# Adafruit_Power_Switch.net
KiCad netlist of a schematic drawn in EAGLE
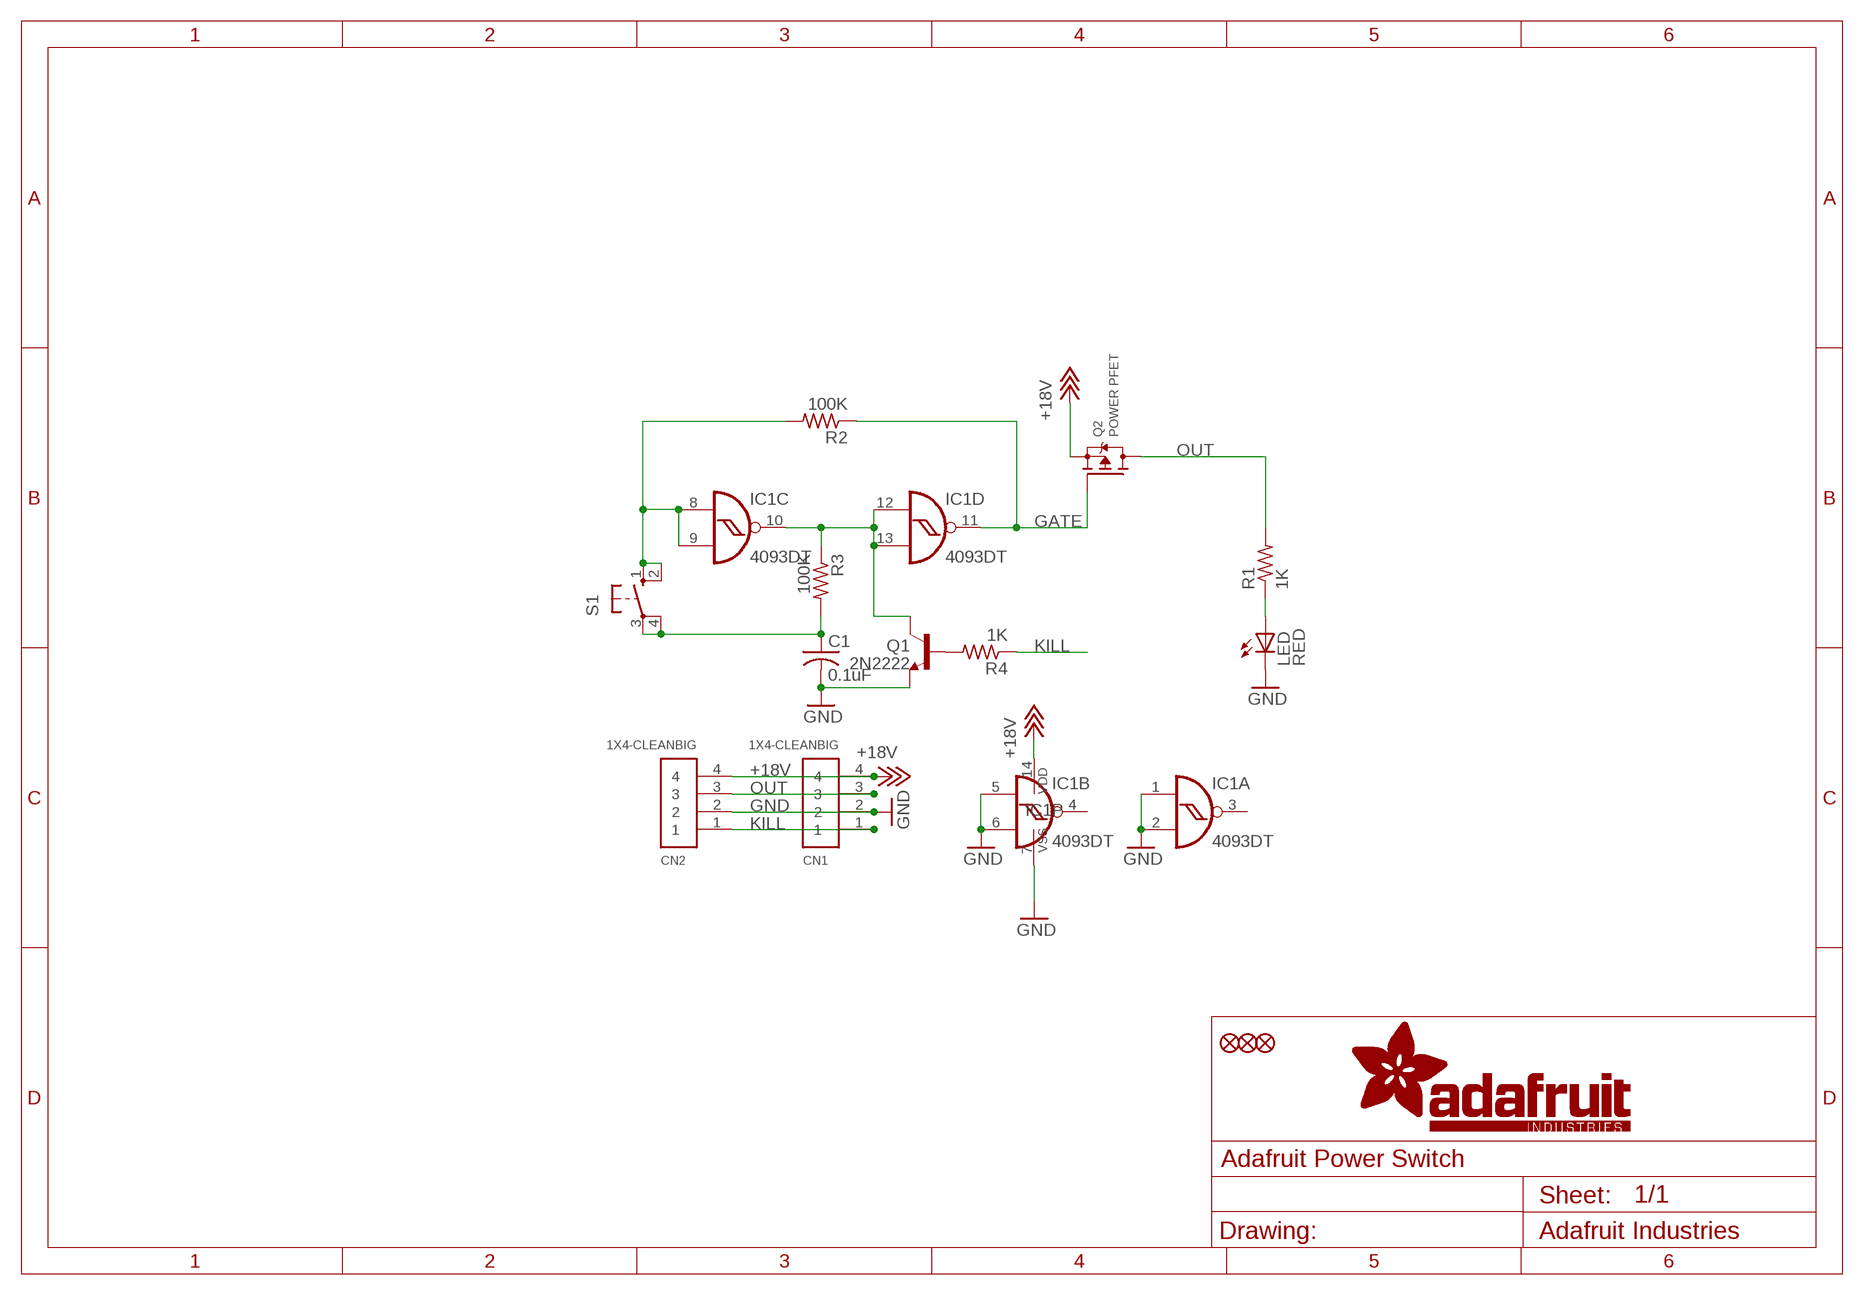
[diagram p0: schematic, sheet 1]

(export (version "E")
  (design (tool "Eeschema 10.0.6"))
  (components
    (comp (ref "C1")
      (value "0.1uF")
      (footprint "eagle-import:C0805")
      (libsource (lib "eagle-import") (part "C-USC0805"))
    )
    (comp (ref "CN1")
      (value "1X4-CLEANBIG")
      (footprint "eagle-import:1X04-CLEANBIG")
      (libsource (lib "eagle-import") (part "1X4-CLEANBIG"))
    )
    (comp (ref "CN2")
      (value "1X4-CLEANBIG")
      (footprint "eagle-import:1X04-CLEANBIG")
      (libsource (lib "eagle-import") (part "1X4-CLEANBIG"))
    )
    (comp (ref "FID1")
      (value "FIDUCIAL\"\"")
      (footprint "eagle-import:FIDUCIAL_1MM")
      (libsource (lib "eagle-import") (part "FIDUCIAL{dblquote}{dblquote}"))
    )
    (comp (ref "FID2")
      (value "FIDUCIAL\"\"")
      (footprint "eagle-import:FIDUCIAL_1MM")
      (libsource (lib "eagle-import") (part "FIDUCIAL{dblquote}{dblquote}"))
    )
    (comp (ref "FID3")
      (value "FIDUCIAL\"\"")
      (footprint "eagle-import:FIDUCIAL_1MM")
      (libsource (lib "eagle-import") (part "FIDUCIAL{dblquote}{dblquote}"))
    )
    (comp (ref "IC1")
      (value "4093DT")
      (footprint "eagle-import:MC14093B-TSSOP14")
      (libsource (lib "eagle-import") (part "4093DT"))
    )
    (comp (ref "LED")
      (value "RED")
      (footprint "eagle-import:CHIP-LED0805")
      (libsource (lib "eagle-import") (part "LEDCHIP-LED0805"))
    )
    (comp (ref "Q1")
      (value "2N2222")
      (footprint "eagle-import:SOT23-BEC")
      (libsource (lib "eagle-import") (part "-NPN-SOT23-BECMMBT2222ALT1"))
    )
    (comp (ref "Q2")
      (value "POWER PFET")
      (footprint "eagle-import:SOT23-WIDE")
      (libsource (lib "eagle-import") (part "MOSFET-PWIDE"))
    )
    (comp (ref "R1")
      (value "1K")
      (footprint "eagle-import:R0805")
      (libsource (lib "eagle-import") (part "rcl_R-US_R0805"))
    )
    (comp (ref "R2")
      (value "100K")
      (footprint "eagle-import:R0805")
      (libsource (lib "eagle-import") (part "rcl_R-US_R0805"))
    )
    (comp (ref "R3")
      (value "100K")
      (footprint "eagle-import:R0805")
      (libsource (lib "eagle-import") (part "rcl_R-US_R0805"))
    )
    (comp (ref "R4")
      (value "1K")
      (footprint "eagle-import:R0805")
      (libsource (lib "eagle-import") (part "R-US_R0805"))
    )
    (comp (ref "S1")
      (value "40-XX-ROUND")
      (footprint "eagle-import:B3F-40XX-ROUND")
      (libsource (lib "eagle-import") (part "40-XX-ROUND"))
    )
  )
  (nets
    (net (code "1") (name "+18V") (class "Default")
      (node (ref "CN1") (pin "4") (pinfunction "4_4") (pintype "bidirectional"))
      (node (ref "CN2") (pin "4") (pinfunction "4_4") (pintype "bidirectional"))
      (node (ref "IC1") (pin "14") (pinfunction "VDD_14") (pintype "power_in"))
      (node (ref "Q2") (pin "2") (pinfunction "S_2") (pintype "passive"))
    )
    (net (code "2") (name "/GATE") (class "Default")
      (node (ref "IC1") (pin "11") (pinfunction "O_11") (pintype "output"))
      (node (ref "Q2") (pin "1") (pinfunction "G_1") (pintype "passive"))
      (node (ref "R2") (pin "1") (pinfunction "1_1") (pintype "passive"))
    )
    (net (code "3") (name "/KILL") (class "Default")
      (node (ref "CN1") (pin "1") (pinfunction "1_1") (pintype "bidirectional"))
      (node (ref "CN2") (pin "1") (pinfunction "1_1") (pintype "bidirectional"))
      (node (ref "R4") (pin "1") (pinfunction "1_1") (pintype "passive"))
    )
    (net (code "4") (name "/OUT") (class "Default")
      (node (ref "CN1") (pin "3") (pinfunction "3_3") (pintype "bidirectional"))
      (node (ref "CN2") (pin "3") (pinfunction "3_3") (pintype "bidirectional"))
      (node (ref "Q2") (pin "3") (pinfunction "D_3") (pintype "passive"))
      (node (ref "R1") (pin "2") (pinfunction "2_2") (pintype "passive"))
    )
    (net (code "5") (name "GND") (class "Default")
      (node (ref "C1") (pin "2") (pinfunction "2_2") (pintype "passive"))
      (node (ref "CN1") (pin "2") (pinfunction "2_2") (pintype "bidirectional"))
      (node (ref "CN2") (pin "2") (pinfunction "2_2") (pintype "bidirectional"))
      (node (ref "IC1") (pin "1") (pinfunction "I0_1") (pintype "input"))
      (node (ref "IC1") (pin "2") (pinfunction "I1_2") (pintype "input"))
      (node (ref "IC1") (pin "5") (pinfunction "I0_5") (pintype "input"))
      (node (ref "IC1") (pin "6") (pinfunction "I1_6") (pintype "input"))
      (node (ref "IC1") (pin "7") (pinfunction "VSS_7") (pintype "power_in"))
      (node (ref "LED") (pin "C") (pinfunction "C_C") (pintype "passive"))
      (node (ref "Q1") (pin "E") (pinfunction "E_E") (pintype "passive"))
    )
    (net (code "6") (name "Net-(IC1C-I0)") (class "Default")
      (node (ref "IC1") (pin "8") (pinfunction "I0_8") (pintype "input"))
      (node (ref "IC1") (pin "9") (pinfunction "I1_9") (pintype "input"))
      (node (ref "R2") (pin "2") (pinfunction "2_2") (pintype "passive"))
      (node (ref "S1") (pin "1") (pinfunction "S_1") (pintype "passive"))
      (node (ref "S1") (pin "2") (pinfunction "S1_2") (pintype "passive"))
    )
    (net (code "7") (name "Net-(IC1C-O)") (class "Default")
      (node (ref "IC1") (pin "10") (pinfunction "O_10") (pintype "output"))
      (node (ref "IC1") (pin "12") (pinfunction "I0_12") (pintype "input"))
      (node (ref "IC1") (pin "13") (pinfunction "I1_13") (pintype "input"))
      (node (ref "Q1") (pin "C") (pinfunction "C_C") (pintype "passive"))
      (node (ref "R3") (pin "1") (pinfunction "1_1") (pintype "passive"))
    )
    (net (code "8") (name "Net-(LED-PadA)") (class "Default")
      (node (ref "LED") (pin "A") (pinfunction "A_A") (pintype "passive"))
      (node (ref "R1") (pin "1") (pinfunction "1_1") (pintype "passive"))
    )
    (net (code "9") (name "Net-(Q1-PadB)") (class "Default")
      (node (ref "Q1") (pin "B") (pinfunction "B_B") (pintype "passive"))
      (node (ref "R4") (pin "2") (pinfunction "2_2") (pintype "passive"))
    )
    (net (code "10") (name "Net-(S1-P)") (class "Default")
      (node (ref "C1") (pin "1") (pinfunction "1_1") (pintype "passive"))
      (node (ref "R3") (pin "2") (pinfunction "2_2") (pintype "passive"))
      (node (ref "S1") (pin "3") (pinfunction "P_3") (pintype "passive"))
      (node (ref "S1") (pin "4") (pinfunction "P1_4") (pintype "passive"))
    )
    (net (code "11") (name "unconnected-(IC1A-O-Pad3)") (class "Default")
      (node (ref "IC1") (pin "3") (pinfunction "O_3") (pintype "output"))
    )
    (net (code "12") (name "unconnected-(IC1B-O-Pad4)") (class "Default")
      (node (ref "IC1") (pin "4") (pinfunction "O_4") (pintype "output"))
    )
  )
)
